# Ethernet.net
KiCad netlist of a schematic drawn in Altium Designer
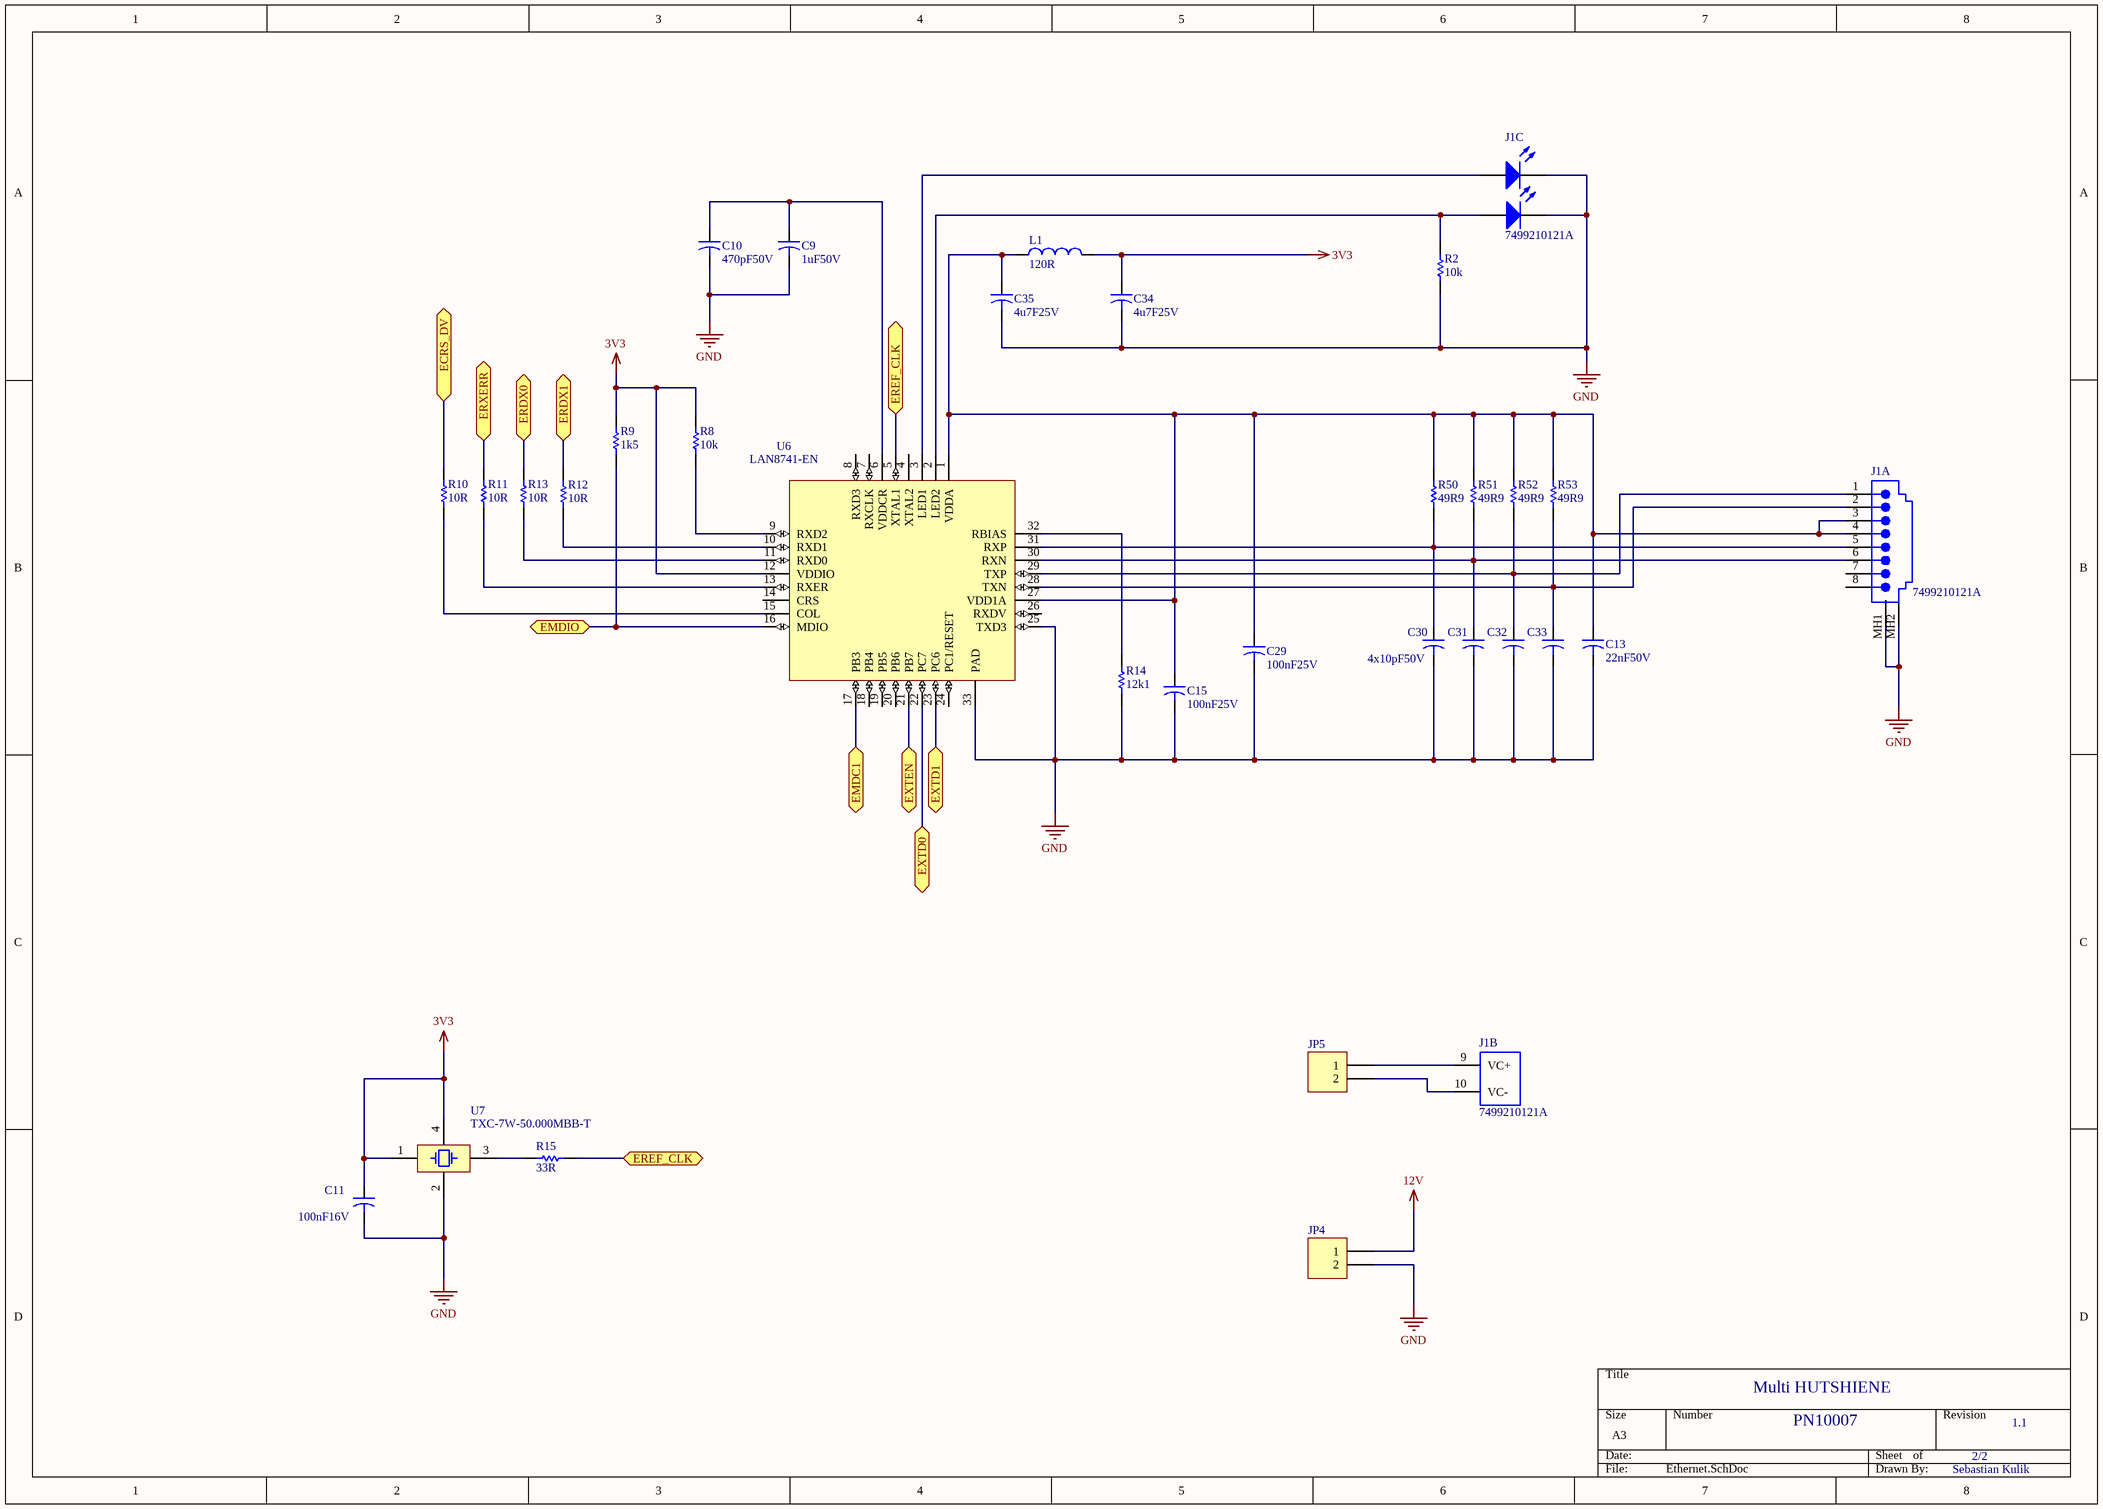
[diagram p0: Ethernet.SchDoc]

(export (version "E")
  (design (tool "Eeschema 10.0.6"))
  (components
    (comp (ref "C9")
      (value "1uF50V")
      (footprint "C0603")
      (description "C series, X5R, 10%")
      (fields
        (field (name "MANUFACTURER") "TDK")
        (field (name "Comment") "1uF50V_0603")
        (field (name "PUBLISHER") "Sebastian Kulik")
      )
      (libsource (lib "Capacitors") (part "1uF50V_0603"))
    )
    (comp (ref "C10")
      (value "470pF50V")
      (footprint "C0402")
      (description "AVX, 50V")
      (fields
        (field (name "MANUFACTURER") "AVX")
        (field (name "Comment") "470pF50V_0402")
        (field (name "PUBLISHER") "Sebastian Kulik")
      )
      (libsource (lib "Capacitors") (part "470pF50V_0402"))
    )
    (comp (ref "C11")
      (value "100nF16V")
      (footprint "C0402")
      (description "Capacitor")
      (fields
        (field (name "MANUFACTURER") "TDK")
        (field (name "Comment") "100nF16V_0402")
        (field (name "PUBLISHER") "Sebastian Kulik")
      )
      (libsource (lib "Capacitors") (part "100nF16V_0402"))
    )
    (comp (ref "C13")
      (value "22nF50V")
      (footprint "C0603")
      (description "AVX ,  X7R, 5%, 50V")
      (fields
        (field (name "MANUFACTURER") "AVX")
        (field (name "Comment") "22nF50V_0603")
        (field (name "PUBLISHER") "Sebastian Kulik")
      )
      (libsource (lib "Capacitors") (part "22nF50V_0603"))
    )
    (comp (ref "C15")
      (value "100nF25V")
      (footprint "C0402")
      (description "AVX, X5R, 10%, 25V")
      (fields
        (field (name "MANUFACTURER") "AVX")
        (field (name "Comment") "100nF25V_0402")
        (field (name "PUBLISHER") "Sebastian Kulik")
      )
      (libsource (lib "Capacitors") (part "100nF25V_0402"))
    )
    (comp (ref "C29")
      (value "100nF25V")
      (footprint "C0402")
      (description "AVX, X5R, 10%, 25V")
      (fields
        (field (name "MANUFACTURER") "AVX")
        (field (name "Comment") "100nF25V_0402")
        (field (name "PUBLISHER") "Sebastian Kulik")
      )
      (libsource (lib "Capacitors") (part "100nF25V_0402"))
    )
    (comp (ref "C30")
      (value "10pF50V_0603")
      (footprint "C0603")
      (description "AVX ,  +-0.5pF, 50V")
      (fields (field (name "MANUFACTURER") "AVX") (field (name "PUBLISHER") "Sebastian Kulik"))
      (libsource (lib "Capacitors") (part "10pF50V_0603"))
    )
    (comp (ref "C31")
      (value "10pF50V_0603")
      (footprint "C0603")
      (description "AVX ,  +-0.5pF, 50V")
      (fields (field (name "MANUFACTURER") "AVX") (field (name "PUBLISHER") "Sebastian Kulik"))
      (libsource (lib "Capacitors") (part "10pF50V_0603"))
    )
    (comp (ref "C32")
      (value "10pF50V_0603")
      (footprint "C0603")
      (description "AVX ,  +-0.5pF, 50V")
      (fields (field (name "MANUFACTURER") "AVX") (field (name "PUBLISHER") "Sebastian Kulik"))
      (libsource (lib "Capacitors") (part "10pF50V_0603"))
    )
    (comp (ref "C33")
      (value "10pF50V_0603")
      (footprint "C0603")
      (description "AVX ,  +-0.5pF, 50V")
      (fields (field (name "MANUFACTURER") "AVX") (field (name "PUBLISHER") "Sebastian Kulik"))
      (libsource (lib "Capacitors") (part "10pF50V_0603"))
    )
    (comp (ref "C34")
      (value "4u7F25V")
      (footprint "C0805")
      (description "TDK  C series, X7R, 10%, 25V")
      (fields
        (field (name "MANUFACTURER") "TDK")
        (field (name "Comment") "4u7F25V_0805")
        (field (name "PUBLISHER") "Sebastian Kulik")
      )
      (libsource (lib "Capacitors") (part "4u7F25V_0805"))
    )
    (comp (ref "C35")
      (value "4u7F25V")
      (footprint "C0805")
      (description "TDK  C series, X7R, 10%, 25V")
      (fields
        (field (name "MANUFACTURER") "TDK")
        (field (name "Comment") "4u7F25V_0805")
        (field (name "PUBLISHER") "Sebastian Kulik")
      )
      (libsource (lib "Capacitors") (part "4u7F25V_0805"))
    )
    (comp (ref "J1")
      (value "7499210121A")
      (footprint "7499210121A")
      (description "Modular Jack , Right Angle RJ-45, Low Profile")
      (fields (field (name "MANUFACTURER") "Wuerth Elektronik") (field (name "PUBLISHER") "Sebastian Kulik"))
      (libsource (lib "Connectors") (part "Ethernet, POE, WE7499210121A"))
    )
    (comp (ref "JP4")
      (value "Header-2")
      (footprint "HDR1X2")
      (description "Header, 5-Pin")
      (fields (field (name "PUBLISHER") "Sebastian Kulik"))
      (libsource (lib "Connectors") (part "Header-2"))
    )
    (comp (ref "JP5")
      (value "Header-2")
      (footprint "HDR1X2")
      (description "Header, 5-Pin")
      (fields (field (name "PUBLISHER") "Sebastian Kulik"))
      (libsource (lib "Connectors") (part "Header-2"))
    )
    (comp (ref "L1")
      (value "120R")
      (footprint "L0603")
      (description "Murata, Ferrit, 120Rx2A")
      (fields
        (field (name "MANUFACTURER") "Murata")
        (field (name "Comment") "120R4A_0603")
        (field (name "PUBLISHER") "Sebastian Kulik")
      )
      (libsource (lib "Passives") (part "120R4A_0603"))
    )
    (comp (ref "R2")
      (value "10k")
      (footprint "R0402")
      (description "Vishay CRCW series, 125mW, 1%")
      (fields
        (field (name "MANUFACTURER") "Vishay")
        (field (name "Comment") "10k_0402")
        (field (name "PUBLISHER") "Sebastian Kulik")
      )
      (libsource (lib "Resistors") (part "10k_0402"))
    )
    (comp (ref "R8")
      (value "10k")
      (footprint "R0402")
      (description "Vishay CRCW series, 125mW, 1%")
      (fields
        (field (name "MANUFACTURER") "Vishay")
        (field (name "Comment") "10k_0402")
        (field (name "PUBLISHER") "Sebastian Kulik")
      )
      (libsource (lib "Resistors") (part "10k_0402"))
    )
    (comp (ref "R9")
      (value "1k5")
      (footprint "R0402")
      (description "Vishay CRCW series, 125mW, 1%")
      (fields
        (field (name "MANUFACTURER") "Vishay")
        (field (name "Comment") "1k5_0402")
        (field (name "PUBLISHER") "Sebastian Kulik")
      )
      (libsource (lib "Resistors") (part "1k5_0402"))
    )
    (comp (ref "R10")
      (value "10R")
      (footprint "R0402")
      (description "Vishay CRCW series, 125mW, 1%")
      (fields
        (field (name "MANUFACTURER") "Vishay")
        (field (name "Comment") "10R_0402")
        (field (name "PUBLISHER") "Sebastian Kulik")
      )
      (libsource (lib "Resistors") (part "10R_0402"))
    )
    (comp (ref "R11")
      (value "10R")
      (footprint "R0402")
      (description "Vishay CRCW series, 125mW, 1%")
      (fields
        (field (name "MANUFACTURER") "Vishay")
        (field (name "Comment") "10R_0402")
        (field (name "PUBLISHER") "Sebastian Kulik")
      )
      (libsource (lib "Resistors") (part "10R_0402"))
    )
    (comp (ref "R12")
      (value "10R")
      (footprint "R0402")
      (description "Vishay CRCW series, 125mW, 1%")
      (fields
        (field (name "MANUFACTURER") "Vishay")
        (field (name "Comment") "10R_0402")
        (field (name "PUBLISHER") "Sebastian Kulik")
      )
      (libsource (lib "Resistors") (part "10R_0402"))
    )
    (comp (ref "R13")
      (value "10R")
      (footprint "R0402")
      (description "Vishay CRCW series, 125mW, 1%")
      (fields
        (field (name "MANUFACTURER") "Vishay")
        (field (name "Comment") "10R_0402")
        (field (name "PUBLISHER") "Sebastian Kulik")
      )
      (libsource (lib "Resistors") (part "10R_0402"))
    )
    (comp (ref "R14")
      (value "12k1")
      (footprint "R0603(1608)")
      (description "Vishay, CRCW series, 100mW, 1%")
      (fields
        (field (name "MANUFACTURER") "Vishay")
        (field (name "Comment") "12k1_0603")
        (field (name "PUBLISHER") "Sebastian Kulik")
      )
      (libsource (lib "Resistors") (part "12k1_0603"))
    )
    (comp (ref "R15")
      (value "33R")
      (footprint "R0402")
      (description "Vishay CRCW series, 63mW, 1%")
      (fields
        (field (name "MANUFACTURER") "Vishay")
        (field (name "Comment") "33R_0402")
        (field (name "PUBLISHER") "Sebastian Kulik")
      )
      (libsource (lib "Resistors") (part "33R_0402"))
    )
    (comp (ref "R50")
      (value "49R9")
      (footprint "R0402")
      (description "Vishay CRCW series, 63mW, 1%")
      (fields
        (field (name "MANUFACTURER") "Vishay")
        (field (name "Comment") "49R9_0402")
        (field (name "PUBLISHER") "Sebastian Kulik")
      )
      (libsource (lib "Resistors") (part "49R9_0402"))
    )
    (comp (ref "R51")
      (value "49R9")
      (footprint "R0402")
      (description "Vishay CRCW series, 63mW, 1%")
      (fields
        (field (name "MANUFACTURER") "Vishay")
        (field (name "Comment") "49R9_0402")
        (field (name "PUBLISHER") "Sebastian Kulik")
      )
      (libsource (lib "Resistors") (part "49R9_0402"))
    )
    (comp (ref "R52")
      (value "49R9")
      (footprint "R0402")
      (description "Vishay CRCW series, 63mW, 1%")
      (fields
        (field (name "MANUFACTURER") "Vishay")
        (field (name "Comment") "49R9_0402")
        (field (name "PUBLISHER") "Sebastian Kulik")
      )
      (libsource (lib "Resistors") (part "49R9_0402"))
    )
    (comp (ref "R53")
      (value "49R9")
      (footprint "R0402")
      (description "Vishay CRCW series, 63mW, 1%")
      (fields
        (field (name "MANUFACTURER") "Vishay")
        (field (name "Comment") "49R9_0402")
        (field (name "PUBLISHER") "Sebastian Kulik")
      )
      (libsource (lib "Resistors") (part "49R9_0402"))
    )
    (comp (ref "U6")
      (value "LAN8741-EN")
      (footprint "32M1-A_M")
      (description "Ethernet Phy")
      (fields (field (name "MANUFACTURER") "Microchip") (field (name "PUBLISHER") "Sebastian Kulik"))
      (libsource (lib "ICs") (part "LAN8741-EN"))
    )
    (comp (ref "U7")
      (value "TXC-7W-50.000MBB-T")
      (footprint "TXC_7W")
      (description "Crystal")
      (fields (field (name "MANUFACTURER") "TXC") (field (name "PUBLISHER") "Sebastian Kulik"))
      (libsource (lib "ICs") (part "TXC-7W-50.000MBB-T"))
    )
  )
  (nets
    (net (code "1") (name "/ECRS_DV") (class "Default")
      (node (ref "R10") (pin "2") (pinfunction "2_2") (pintype "passive"))
    )
    (net (code "2") (name "/EMDC1") (class "Default")
      (node (ref "U6") (pin "17") (pinfunction "PB3_17") (pintype "bidirectional"))
    )
    (net (code "3") (name "/EMDIO") (class "Default")
      (node (ref "R9") (pin "1") (pinfunction "1_1") (pintype "passive"))
      (node (ref "U6") (pin "16") (pinfunction "MDIO_16") (pintype "bidirectional"))
    )
    (net (code "4") (name "/ERDX0") (class "Default")
      (node (ref "R13") (pin "2") (pinfunction "2_2") (pintype "passive"))
    )
    (net (code "5") (name "/ERDX1") (class "Default")
      (node (ref "R12") (pin "1") (pinfunction "1_1") (pintype "passive"))
    )
    (net (code "6") (name "/EREF_CLK") (class "Default")
      (node (ref "R15") (pin "2") (pinfunction "2_2") (pintype "passive"))
      (node (ref "U6") (pin "5") (pinfunction "XTAL1_5") (pintype "bidirectional"))
    )
    (net (code "7") (name "/ERXERR") (class "Default")
      (node (ref "R11") (pin "2") (pinfunction "2_2") (pintype "passive"))
    )
    (net (code "8") (name "/EXTD0") (class "Default")
      (node (ref "U6") (pin "22") (pinfunction "PC7_22") (pintype "bidirectional"))
    )
    (net (code "9") (name "/EXTD1") (class "Default")
      (node (ref "U6") (pin "23") (pinfunction "PC6_23") (pintype "bidirectional"))
    )
    (net (code "10") (name "/EXTEN") (class "Default")
      (node (ref "U6") (pin "21") (pinfunction "PB7_21") (pintype "bidirectional"))
    )
    (net (code "11") (name "3V3") (class "Default")
      (node (ref "C11") (pin "1") (pinfunction "1_1") (pintype "passive"))
      (node (ref "C34") (pin "1") (pinfunction "1_1") (pintype "passive"))
      (node (ref "L1") (pin "2") (pinfunction "2_2") (pintype "passive"))
      (node (ref "R8") (pin "2") (pinfunction "2_2") (pintype "passive"))
      (node (ref "R9") (pin "2") (pinfunction "2_2") (pintype "passive"))
      (node (ref "U6") (pin "12") (pinfunction "VDDIO_12") (pintype "passive"))
      (node (ref "U7") (pin "1") (pinfunction "E/D_1") (pintype "passive"))
      (node (ref "U7") (pin "4") (pinfunction "VCC_4") (pintype "passive"))
    )
    (net (code "12") (name "12V") (class "Default")
      (node (ref "JP4") (pin "1") (pinfunction "1_1") (pintype "passive"))
    )
    (net (code "13") (name "GND") (class "Default")
      (node (ref "C10") (pin "2") (pinfunction "2_2") (pintype "passive"))
      (node (ref "C11") (pin "2") (pinfunction "2_2") (pintype "passive"))
      (node (ref "C13") (pin "2") (pinfunction "2_2") (pintype "passive"))
      (node (ref "C15") (pin "2") (pinfunction "2_2") (pintype "passive"))
      (node (ref "C29") (pin "2") (pinfunction "2_2") (pintype "passive"))
      (node (ref "C30") (pin "2") (pinfunction "2_2") (pintype "passive"))
      (node (ref "C31") (pin "2") (pinfunction "2_2") (pintype "passive"))
      (node (ref "C32") (pin "2") (pinfunction "2_2") (pintype "passive"))
      (node (ref "C33") (pin "2") (pinfunction "2_2") (pintype "passive"))
      (node (ref "C34") (pin "2") (pinfunction "2_2") (pintype "passive"))
      (node (ref "C35") (pin "2") (pinfunction "2_2") (pintype "passive"))
      (node (ref "C9") (pin "2") (pinfunction "2_2") (pintype "passive"))
      (node (ref "J1") (pin "12") (pinfunction "K_12") (pintype "passive"))
      (node (ref "J1") (pin "14") (pinfunction "K_14") (pintype "passive"))
      (node (ref "J1") (pin "MH1") (pinfunction "Shield_MH1") (pintype "passive"))
      (node (ref "J1") (pin "MH2") (pinfunction "Shield_MH2") (pintype "passive"))
      (node (ref "JP4") (pin "2") (pinfunction "2_2") (pintype "passive"))
      (node (ref "R14") (pin "1") (pinfunction "1_1") (pintype "passive"))
      (node (ref "R2") (pin "1") (pinfunction "1_1") (pintype "passive"))
      (node (ref "U6") (pin "25") (pinfunction "TXD3_25") (pintype "bidirectional"))
      (node (ref "U6") (pin "33") (pinfunction "PAD_33") (pintype "power_in"))
      (node (ref "U7") (pin "2") (pinfunction "GND_2") (pintype "passive"))
    )
    (net (code "14") (name "Net-(J1B-VC+)") (class "Default")
      (node (ref "J1") (pin "9") (pinfunction "VC+_9") (pintype "passive"))
      (node (ref "JP5") (pin "1") (pinfunction "1_1") (pintype "passive"))
    )
    (net (code "15") (name "Net-(J1B-VC-)") (class "Default")
      (node (ref "J1") (pin "10") (pinfunction "VC-_10") (pintype "passive"))
      (node (ref "JP5") (pin "2") (pinfunction "2_2") (pintype "passive"))
    )
    (net (code "16") (name "Net-(U6-COL)") (class "Default")
      (node (ref "R10") (pin "1") (pinfunction "1_1") (pintype "passive"))
      (node (ref "U6") (pin "15") (pinfunction "COL_15") (pintype "passive"))
    )
    (net (code "17") (name "Net-(U6-LED1)") (class "Default")
      (node (ref "J1") (pin "11") (pinfunction "A_11") (pintype "passive"))
      (node (ref "U6") (pin "3") (pinfunction "LED1_3") (pintype "power_in"))
    )
    (net (code "18") (name "Net-(U6-LED2)") (class "Default")
      (node (ref "J1") (pin "13") (pinfunction "A_13") (pintype "passive"))
      (node (ref "R2") (pin "2") (pinfunction "2_2") (pintype "passive"))
      (node (ref "U6") (pin "2") (pinfunction "LED2_2") (pintype "passive"))
    )
    (net (code "19") (name "Net-(U6-RBIAS)") (class "Default")
      (node (ref "R14") (pin "2") (pinfunction "2_2") (pintype "passive"))
      (node (ref "U6") (pin "32") (pinfunction "RBIAS_32") (pintype "power_in"))
    )
    (net (code "20") (name "Net-(U6-RXD0)") (class "Default")
      (node (ref "R13") (pin "1") (pinfunction "1_1") (pintype "passive"))
      (node (ref "U6") (pin "11") (pinfunction "RXD0_11") (pintype "bidirectional"))
    )
    (net (code "21") (name "Net-(U6-RXD1)") (class "Default")
      (node (ref "R12") (pin "2") (pinfunction "2_2") (pintype "passive"))
      (node (ref "U6") (pin "10") (pinfunction "RXD1_10") (pintype "bidirectional"))
    )
    (net (code "22") (name "Net-(U6-RXD2)") (class "Default")
      (node (ref "R8") (pin "1") (pinfunction "1_1") (pintype "passive"))
      (node (ref "U6") (pin "9") (pinfunction "RXD2_9") (pintype "bidirectional"))
    )
    (net (code "23") (name "Net-(U6-RXER)") (class "Default")
      (node (ref "R11") (pin "1") (pinfunction "1_1") (pintype "passive"))
      (node (ref "U6") (pin "13") (pinfunction "RXER_13") (pintype "bidirectional"))
    )
    (net (code "24") (name "Net-(U6-RXN)") (class "Default")
      (node (ref "C31") (pin "1") (pinfunction "1_1") (pintype "passive"))
      (node (ref "J1") (pin "6") (pinfunction "6_6") (pintype "passive"))
      (node (ref "R51") (pin "1") (pinfunction "1_1") (pintype "passive"))
      (node (ref "U6") (pin "30") (pinfunction "RXN_30") (pintype "passive"))
    )
    (net (code "25") (name "Net-(U6-RXP)") (class "Default")
      (node (ref "C30") (pin "1") (pinfunction "1_1") (pintype "passive"))
      (node (ref "J1") (pin "5") (pinfunction "5_5") (pintype "passive"))
      (node (ref "R50") (pin "1") (pinfunction "1_1") (pintype "passive"))
      (node (ref "U6") (pin "31") (pinfunction "RXP_31") (pintype "passive"))
    )
    (net (code "26") (name "Net-(U6-TXN)") (class "Default")
      (node (ref "C33") (pin "1") (pinfunction "1_1") (pintype "passive"))
      (node (ref "J1") (pin "2") (pinfunction "2_2") (pintype "passive"))
      (node (ref "R53") (pin "1") (pinfunction "1_1") (pintype "passive"))
      (node (ref "U6") (pin "28") (pinfunction "TXN_28") (pintype "bidirectional"))
    )
    (net (code "27") (name "Net-(U6-TXP)") (class "Default")
      (node (ref "C32") (pin "1") (pinfunction "1_1") (pintype "passive"))
      (node (ref "J1") (pin "1") (pinfunction "1_1") (pintype "passive"))
      (node (ref "R52") (pin "1") (pinfunction "1_1") (pintype "passive"))
      (node (ref "U6") (pin "29") (pinfunction "TXP_29") (pintype "bidirectional"))
    )
    (net (code "28") (name "Net-(U6-VDD1A)") (class "Default")
      (node (ref "C13") (pin "1") (pinfunction "1_1") (pintype "passive"))
      (node (ref "C15") (pin "1") (pinfunction "1_1") (pintype "passive"))
      (node (ref "C29") (pin "1") (pinfunction "1_1") (pintype "passive"))
      (node (ref "C35") (pin "1") (pinfunction "1_1") (pintype "passive"))
      (node (ref "J1") (pin "3") (pinfunction "3_3") (pintype "passive"))
      (node (ref "J1") (pin "4") (pinfunction "4_4") (pintype "passive"))
      (node (ref "L1") (pin "1") (pinfunction "1_1") (pintype "passive"))
      (node (ref "R50") (pin "2") (pinfunction "2_2") (pintype "passive"))
      (node (ref "R51") (pin "2") (pinfunction "2_2") (pintype "passive"))
      (node (ref "R52") (pin "2") (pinfunction "2_2") (pintype "passive"))
      (node (ref "R53") (pin "2") (pinfunction "2_2") (pintype "passive"))
      (node (ref "U6") (pin "1") (pinfunction "VDDA_1") (pintype "passive"))
      (node (ref "U6") (pin "27") (pinfunction "VDD1A_27") (pintype "passive"))
    )
    (net (code "29") (name "Net-(U6-VDDCR)") (class "Default")
      (node (ref "C10") (pin "1") (pinfunction "1_1") (pintype "passive"))
      (node (ref "C9") (pin "1") (pinfunction "1_1") (pintype "passive"))
      (node (ref "U6") (pin "6") (pinfunction "VDDCR_6") (pintype "passive"))
    )
    (net (code "30") (name "Net-(U7-OSC2)") (class "Default")
      (node (ref "R15") (pin "1") (pinfunction "1_1") (pintype "passive"))
      (node (ref "U7") (pin "3") (pinfunction "OSC2_3") (pintype "passive"))
    )
    (net (code "31") (name "unconnected-(J1-Pad7)") (class "Default")
      (node (ref "J1") (pin "7") (pinfunction "7_7") (pintype "passive"))
    )
    (net (code "32") (name "unconnected-(J1-Pad8)") (class "Default")
      (node (ref "J1") (pin "8") (pinfunction "8_8") (pintype "passive"))
    )
    (net (code "33") (name "unconnected-(U6-CRS-Pad14)") (class "Default")
      (node (ref "U6") (pin "14") (pinfunction "CRS_14") (pintype "passive"))
    )
    (net (code "34") (name "unconnected-(U6-PB4-Pad18)") (class "Default")
      (node (ref "U6") (pin "18") (pinfunction "PB4_18") (pintype "bidirectional"))
    )
    (net (code "35") (name "unconnected-(U6-PB5-Pad19)") (class "Default")
      (node (ref "U6") (pin "19") (pinfunction "PB5_19") (pintype "bidirectional"))
    )
    (net (code "36") (name "unconnected-(U6-PB6-Pad20)") (class "Default")
      (node (ref "U6") (pin "20") (pinfunction "PB6_20") (pintype "bidirectional"))
    )
    (net (code "37") (name "unconnected-(U6-PC1{slash}RESET-Pad24)") (class "Default")
      (node (ref "U6") (pin "24") (pinfunction "PC1/RESET_24") (pintype "bidirectional"))
    )
    (net (code "38") (name "unconnected-(U6-RXCLK-Pad7)") (class "Default")
      (node (ref "U6") (pin "7") (pinfunction "RXCLK_7") (pintype "bidirectional"))
    )
    (net (code "39") (name "unconnected-(U6-RXD3-Pad8)") (class "Default")
      (node (ref "U6") (pin "8") (pinfunction "RXD3_8") (pintype "bidirectional"))
    )
    (net (code "40") (name "unconnected-(U6-RXDV-Pad26)") (class "Default")
      (node (ref "U6") (pin "26") (pinfunction "RXDV_26") (pintype "bidirectional"))
    )
    (net (code "41") (name "unconnected-(U6-XTAL2-Pad4)") (class "Default")
      (node (ref "U6") (pin "4") (pinfunction "XTAL2_4") (pintype "power_in"))
    )
  )
)
